# MDCC_1024k.net
KiCad netlist of a schematic drawn in EAGLE
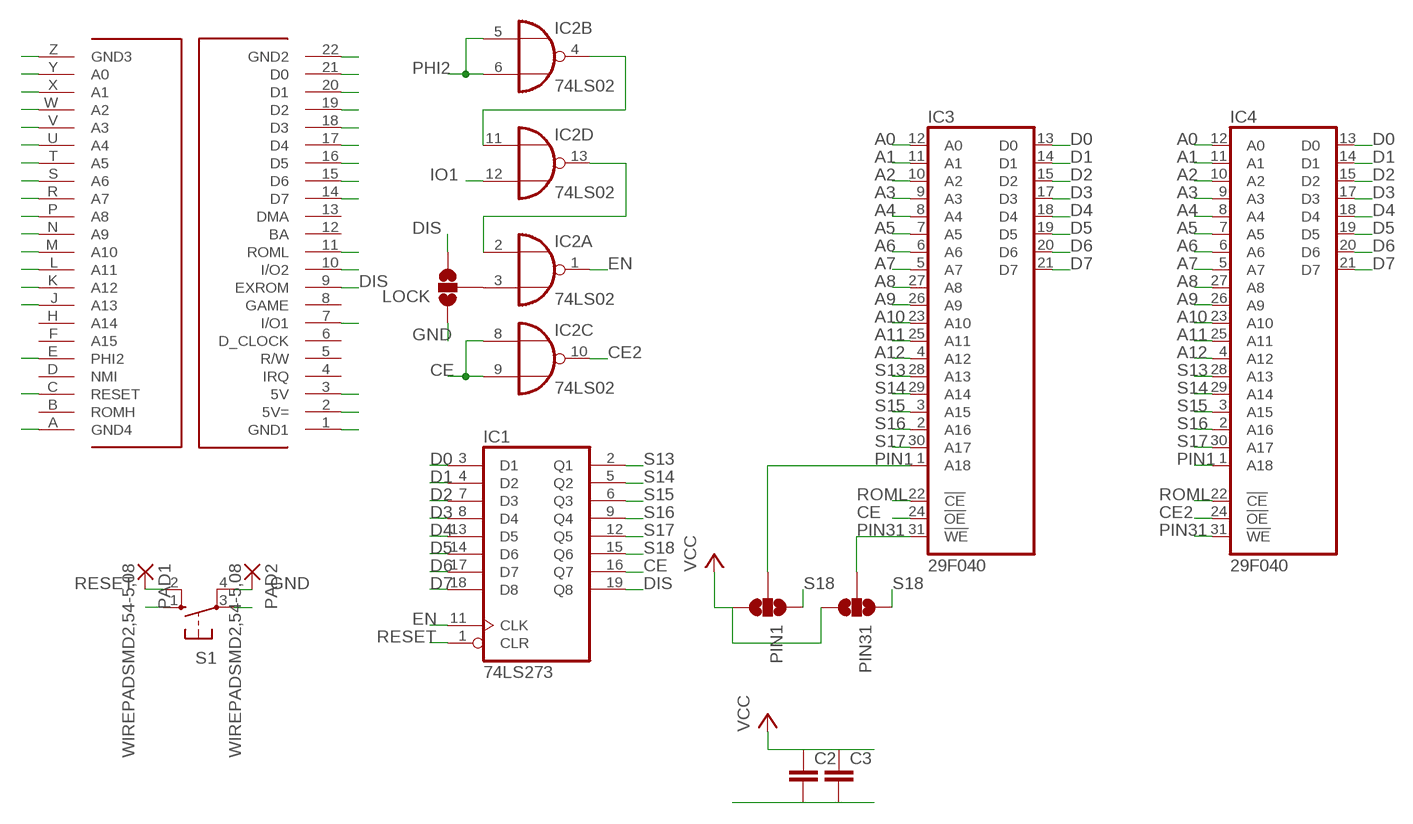
[diagram p0: schematic, sheet 1]

(export (version "E")
  (design (tool "Eeschema 10.0.6"))
  (components
    (comp (ref "C2")
      (value "C-EU025-024X044")
      (footprint "eagle-import:C025-024X044")
      (libsource (lib "eagle-import") (part "C-EU025-024X044"))
    )
    (comp (ref "C3")
      (value "C-EU025-024X044")
      (footprint "eagle-import:C025-024X044")
      (libsource (lib "eagle-import") (part "C-EU025-024X044"))
    )
    (comp (ref "IC1")
      (value "74LS273")
      (footprint "eagle-import:DIL20")
      (libsource (lib "eagle-import") (part "74273NHCT"))
    )
    (comp (ref "IC2")
      (value "74LS02")
      (footprint "eagle-import:DIL14")
      (libsource (lib "eagle-import") (part "7402NLS"))
    )
    (comp (ref "IC3")
      (value "29F040")
      (footprint "eagle-import:DIL32-6")
      (libsource (lib "eagle-import") (part "AM29F040N"))
    )
    (comp (ref "IC4")
      (value "29F040")
      (footprint "eagle-import:DIL32-6")
      (libsource (lib "eagle-import") (part "AM29F040N"))
    )
    (comp (ref "LOCK")
      (value "SOLDERJUMPER_2WAYS")
      (footprint "eagle-import:SJ_3")
      (libsource (lib "eagle-import") (part "SOLDERJUMPER_2WAYS"))
    )
    (comp (ref "PAD1")
      (value "WIREPADSMD2,54-5,08")
      (footprint "eagle-import:SMD2,54-5,08")
      (libsource (lib "eagle-import") (part "WIREPADSMD2,54-5,08"))
    )
    (comp (ref "PAD2")
      (value "WIREPADSMD2,54-5,08")
      (footprint "eagle-import:SMD2,54-5,08")
      (libsource (lib "eagle-import") (part "WIREPADSMD2,54-5,08"))
    )
    (comp (ref "PIN1")
      (value "SOLDERJUMPER_2WAYS")
      (footprint "eagle-import:SJ_3")
      (libsource (lib "eagle-import") (part "SOLDERJUMPER_2WAYS"))
    )
    (comp (ref "PIN31")
      (value "SOLDERJUMPER_2WAYS")
      (footprint "eagle-import:SJ_3")
      (libsource (lib "eagle-import") (part "SOLDERJUMPER_2WAYS"))
    )
    (comp (ref "S1")
      (value "10-XX")
      (footprint "eagle-import:B3F-10XX")
      (fields (field (name "MPN") "B3F-1000"))
      (libsource (lib "eagle-import") (part "10-XX"))
    )
    (comp (ref "U$1")
      (value "C64_EXPANSION__CARTRIDGE")
      (footprint "eagle-import:C64_EXPANSION__CARTRIDGE")
      (libsource (lib "eagle-import") (part "C64_EXPANSION__CARTRIDGE"))
    )
  )
  (nets
    (net (code "1") (name "/A0") (class "Default")
      (node (ref "IC3") (pin "12") (pinfunction "A0_12") (pintype "input"))
      (node (ref "IC4") (pin "12") (pinfunction "A0_12") (pintype "input"))
      (node (ref "U$1") (pin "Y") (pinfunction "A0_Y") (pintype "bidirectional"))
    )
    (net (code "2") (name "/A1") (class "Default")
      (node (ref "IC3") (pin "11") (pinfunction "A1_11") (pintype "input"))
      (node (ref "IC4") (pin "11") (pinfunction "A1_11") (pintype "input"))
      (node (ref "U$1") (pin "X") (pinfunction "A1_X") (pintype "bidirectional"))
    )
    (net (code "3") (name "/A2") (class "Default")
      (node (ref "IC3") (pin "10") (pinfunction "A2_10") (pintype "input"))
      (node (ref "IC4") (pin "10") (pinfunction "A2_10") (pintype "input"))
      (node (ref "U$1") (pin "W") (pinfunction "A2_W") (pintype "bidirectional"))
    )
    (net (code "4") (name "/A3") (class "Default")
      (node (ref "IC3") (pin "9") (pinfunction "A3_9") (pintype "input"))
      (node (ref "IC4") (pin "9") (pinfunction "A3_9") (pintype "input"))
      (node (ref "U$1") (pin "V") (pinfunction "A3_V") (pintype "bidirectional"))
    )
    (net (code "5") (name "/A4") (class "Default")
      (node (ref "IC3") (pin "8") (pinfunction "A4_8") (pintype "input"))
      (node (ref "IC4") (pin "8") (pinfunction "A4_8") (pintype "input"))
      (node (ref "U$1") (pin "U") (pinfunction "A4_U") (pintype "bidirectional"))
    )
    (net (code "6") (name "/A5") (class "Default")
      (node (ref "IC3") (pin "7") (pinfunction "A5_7") (pintype "input"))
      (node (ref "IC4") (pin "7") (pinfunction "A5_7") (pintype "input"))
      (node (ref "U$1") (pin "T") (pinfunction "A5_T") (pintype "bidirectional"))
    )
    (net (code "7") (name "/A6") (class "Default")
      (node (ref "IC3") (pin "6") (pinfunction "A6_6") (pintype "input"))
      (node (ref "IC4") (pin "6") (pinfunction "A6_6") (pintype "input"))
      (node (ref "U$1") (pin "S") (pinfunction "A6_S") (pintype "bidirectional"))
    )
    (net (code "8") (name "/A7") (class "Default")
      (node (ref "IC3") (pin "5") (pinfunction "A7_5") (pintype "input"))
      (node (ref "IC4") (pin "5") (pinfunction "A7_5") (pintype "input"))
      (node (ref "U$1") (pin "R") (pinfunction "A7_R") (pintype "bidirectional"))
    )
    (net (code "9") (name "/A8") (class "Default")
      (node (ref "IC3") (pin "27") (pinfunction "A8_27") (pintype "input"))
      (node (ref "IC4") (pin "27") (pinfunction "A8_27") (pintype "input"))
      (node (ref "U$1") (pin "P") (pinfunction "A8_P") (pintype "bidirectional"))
    )
    (net (code "10") (name "/A9") (class "Default")
      (node (ref "IC3") (pin "26") (pinfunction "A9_26") (pintype "input"))
      (node (ref "IC4") (pin "26") (pinfunction "A9_26") (pintype "input"))
      (node (ref "U$1") (pin "N") (pinfunction "A9_N") (pintype "bidirectional"))
    )
    (net (code "11") (name "/A10") (class "Default")
      (node (ref "IC3") (pin "23") (pinfunction "A10_23") (pintype "input"))
      (node (ref "IC4") (pin "23") (pinfunction "A10_23") (pintype "input"))
      (node (ref "U$1") (pin "M") (pinfunction "A10_M") (pintype "bidirectional"))
    )
    (net (code "12") (name "/A11") (class "Default")
      (node (ref "IC3") (pin "25") (pinfunction "A11_25") (pintype "input"))
      (node (ref "IC4") (pin "25") (pinfunction "A11_25") (pintype "input"))
      (node (ref "U$1") (pin "L") (pinfunction "A11_L") (pintype "bidirectional"))
    )
    (net (code "13") (name "/A12") (class "Default")
      (node (ref "IC3") (pin "4") (pinfunction "A12_4") (pintype "input"))
      (node (ref "IC4") (pin "4") (pinfunction "A12_4") (pintype "input"))
      (node (ref "U$1") (pin "K") (pinfunction "A12_K") (pintype "bidirectional"))
    )
    (net (code "14") (name "/CE") (class "Default")
      (node (ref "IC1") (pin "16") (pinfunction "Q7_16") (pintype "output"))
      (node (ref "IC2") (pin "8") (pinfunction "I0_8") (pintype "input"))
      (node (ref "IC2") (pin "9") (pinfunction "I1_9") (pintype "input"))
      (node (ref "IC3") (pin "24") (pinfunction "~{OE}_24") (pintype "input"))
    )
    (net (code "15") (name "/CE2") (class "Default")
      (node (ref "IC2") (pin "10") (pinfunction "O_10") (pintype "output"))
      (node (ref "IC4") (pin "24") (pinfunction "~{OE}_24") (pintype "input"))
    )
    (net (code "16") (name "/D0") (class "Default")
      (node (ref "IC1") (pin "3") (pinfunction "D1_3") (pintype "input"))
      (node (ref "IC3") (pin "13") (pinfunction "D0_13") (pintype "tri_state"))
      (node (ref "IC4") (pin "13") (pinfunction "D0_13") (pintype "tri_state"))
      (node (ref "U$1") (pin "21") (pinfunction "D0_21") (pintype "bidirectional"))
    )
    (net (code "17") (name "/D1") (class "Default")
      (node (ref "IC1") (pin "4") (pinfunction "D2_4") (pintype "input"))
      (node (ref "IC3") (pin "14") (pinfunction "D1_14") (pintype "tri_state"))
      (node (ref "IC4") (pin "14") (pinfunction "D1_14") (pintype "tri_state"))
      (node (ref "U$1") (pin "20") (pinfunction "D1_20") (pintype "bidirectional"))
    )
    (net (code "18") (name "/D2") (class "Default")
      (node (ref "IC1") (pin "7") (pinfunction "D3_7") (pintype "input"))
      (node (ref "IC3") (pin "15") (pinfunction "D2_15") (pintype "tri_state"))
      (node (ref "IC4") (pin "15") (pinfunction "D2_15") (pintype "tri_state"))
      (node (ref "U$1") (pin "19") (pinfunction "D2_19") (pintype "bidirectional"))
    )
    (net (code "19") (name "/D3") (class "Default")
      (node (ref "IC1") (pin "8") (pinfunction "D4_8") (pintype "input"))
      (node (ref "IC3") (pin "17") (pinfunction "D3_17") (pintype "tri_state"))
      (node (ref "IC4") (pin "17") (pinfunction "D3_17") (pintype "tri_state"))
      (node (ref "U$1") (pin "18") (pinfunction "D3_18") (pintype "bidirectional"))
    )
    (net (code "20") (name "/D4") (class "Default")
      (node (ref "IC1") (pin "13") (pinfunction "D5_13") (pintype "input"))
      (node (ref "IC3") (pin "18") (pinfunction "D4_18") (pintype "tri_state"))
      (node (ref "IC4") (pin "18") (pinfunction "D4_18") (pintype "tri_state"))
      (node (ref "U$1") (pin "17") (pinfunction "D4_17") (pintype "bidirectional"))
    )
    (net (code "21") (name "/D5") (class "Default")
      (node (ref "IC1") (pin "14") (pinfunction "D6_14") (pintype "input"))
      (node (ref "IC3") (pin "19") (pinfunction "D5_19") (pintype "tri_state"))
      (node (ref "IC4") (pin "19") (pinfunction "D5_19") (pintype "tri_state"))
      (node (ref "U$1") (pin "16") (pinfunction "D5_16") (pintype "bidirectional"))
    )
    (net (code "22") (name "/D6") (class "Default")
      (node (ref "IC1") (pin "17") (pinfunction "D7_17") (pintype "input"))
      (node (ref "IC3") (pin "20") (pinfunction "D6_20") (pintype "tri_state"))
      (node (ref "IC4") (pin "20") (pinfunction "D6_20") (pintype "tri_state"))
      (node (ref "U$1") (pin "15") (pinfunction "D6_15") (pintype "bidirectional"))
    )
    (net (code "23") (name "/D7") (class "Default")
      (node (ref "IC1") (pin "18") (pinfunction "D8_18") (pintype "input"))
      (node (ref "IC3") (pin "21") (pinfunction "D7_21") (pintype "tri_state"))
      (node (ref "IC4") (pin "21") (pinfunction "D7_21") (pintype "tri_state"))
      (node (ref "U$1") (pin "14") (pinfunction "D7_14") (pintype "bidirectional"))
    )
    (net (code "24") (name "/DIS") (class "Default")
      (node (ref "IC1") (pin "19") (pinfunction "Q8_19") (pintype "output"))
      (node (ref "LOCK") (pin "3") (pinfunction "3_3") (pintype "passive"))
      (node (ref "U$1") (pin "9") (pinfunction "EXROM_9") (pintype "bidirectional"))
    )
    (net (code "25") (name "/EN") (class "Default")
      (node (ref "IC1") (pin "11") (pinfunction "CLK_11") (pintype "input"))
      (node (ref "IC2") (pin "1") (pinfunction "O_1") (pintype "output"))
    )
    (net (code "26") (name "/GND") (class "Default")
      (node (ref "C2") (pin "2") (pinfunction "2_2") (pintype "passive"))
      (node (ref "C3") (pin "2") (pinfunction "2_2") (pintype "passive"))
      (node (ref "LOCK") (pin "1") (pinfunction "1_1") (pintype "passive"))
      (node (ref "PAD2") (pin "1") (pinfunction "P_1") (pintype "passive"))
      (node (ref "S1") (pin "3") (pinfunction "P_3") (pintype "passive"))
      (node (ref "S1") (pin "4") (pinfunction "P1_4") (pintype "passive"))
      (node (ref "U$1") (pin "1") (pinfunction "GND1_1") (pintype "bidirectional"))
      (node (ref "U$1") (pin "22") (pinfunction "GND2_22") (pintype "bidirectional"))
      (node (ref "U$1") (pin "A") (pinfunction "GND4_A") (pintype "bidirectional"))
      (node (ref "U$1") (pin "Z") (pinfunction "GND3_Z") (pintype "bidirectional"))
    )
    (net (code "27") (name "/IO1") (class "Default")
      (node (ref "IC2") (pin "12") (pinfunction "I1_12") (pintype "input"))
      (node (ref "U$1") (pin "7") (pinfunction "I/O1_7") (pintype "bidirectional"))
    )
    (net (code "28") (name "/PHI2") (class "Default")
      (node (ref "IC2") (pin "5") (pinfunction "I0_5") (pintype "input"))
      (node (ref "IC2") (pin "6") (pinfunction "I1_6") (pintype "input"))
      (node (ref "U$1") (pin "E") (pinfunction "PHI2_E") (pintype "bidirectional"))
    )
    (net (code "29") (name "/PIN1") (class "Default")
      (node (ref "IC3") (pin "1") (pinfunction "A18_1") (pintype "input"))
      (node (ref "IC4") (pin "1") (pinfunction "A18_1") (pintype "input"))
      (node (ref "PIN1") (pin "2") (pinfunction "2_2") (pintype "passive"))
    )
    (net (code "30") (name "/PIN31") (class "Default")
      (node (ref "IC3") (pin "31") (pinfunction "~{WE}_31") (pintype "input"))
      (node (ref "IC4") (pin "31") (pinfunction "~{WE}_31") (pintype "input"))
      (node (ref "PIN31") (pin "2") (pinfunction "2_2") (pintype "passive"))
    )
    (net (code "31") (name "/RESET") (class "Default")
      (node (ref "IC1") (pin "1") (pinfunction "CLR_1") (pintype "input"))
      (node (ref "PAD1") (pin "1") (pinfunction "P_1") (pintype "passive"))
      (node (ref "S1") (pin "1") (pinfunction "S_1") (pintype "passive"))
      (node (ref "S1") (pin "2") (pinfunction "S1_2") (pintype "passive"))
      (node (ref "U$1") (pin "C") (pinfunction "RESET_C") (pintype "bidirectional"))
    )
    (net (code "32") (name "/ROML") (class "Default")
      (node (ref "IC3") (pin "22") (pinfunction "~{CE}_22") (pintype "input"))
      (node (ref "IC4") (pin "22") (pinfunction "~{CE}_22") (pintype "input"))
      (node (ref "U$1") (pin "11") (pinfunction "ROML_11") (pintype "bidirectional"))
    )
    (net (code "33") (name "/S13") (class "Default")
      (node (ref "IC1") (pin "2") (pinfunction "Q1_2") (pintype "output"))
      (node (ref "IC3") (pin "28") (pinfunction "A13_28") (pintype "input"))
      (node (ref "IC4") (pin "28") (pinfunction "A13_28") (pintype "input"))
    )
    (net (code "34") (name "/S14") (class "Default")
      (node (ref "IC1") (pin "5") (pinfunction "Q2_5") (pintype "output"))
      (node (ref "IC3") (pin "29") (pinfunction "A14_29") (pintype "input"))
      (node (ref "IC4") (pin "29") (pinfunction "A14_29") (pintype "input"))
    )
    (net (code "35") (name "/S15") (class "Default")
      (node (ref "IC1") (pin "6") (pinfunction "Q3_6") (pintype "output"))
      (node (ref "IC3") (pin "3") (pinfunction "A15_3") (pintype "input"))
      (node (ref "IC4") (pin "3") (pinfunction "A15_3") (pintype "input"))
    )
    (net (code "36") (name "/S16") (class "Default")
      (node (ref "IC1") (pin "9") (pinfunction "Q4_9") (pintype "output"))
      (node (ref "IC3") (pin "2") (pinfunction "A16_2") (pintype "input"))
      (node (ref "IC4") (pin "2") (pinfunction "A16_2") (pintype "input"))
    )
    (net (code "37") (name "/S17") (class "Default")
      (node (ref "IC1") (pin "12") (pinfunction "Q5_12") (pintype "output"))
      (node (ref "IC3") (pin "30") (pinfunction "A17_30") (pintype "input"))
      (node (ref "IC4") (pin "30") (pinfunction "A17_30") (pintype "input"))
    )
    (net (code "38") (name "/S18") (class "Default")
      (node (ref "IC1") (pin "15") (pinfunction "Q6_15") (pintype "output"))
      (node (ref "PIN1") (pin "1") (pinfunction "1_1") (pintype "passive"))
      (node (ref "PIN31") (pin "1") (pinfunction "1_1") (pintype "passive"))
    )
    (net (code "39") (name "Net-(IC2A-I0)") (class "Default")
      (node (ref "IC2") (pin "13") (pinfunction "O_13") (pintype "output"))
      (node (ref "IC2") (pin "2") (pinfunction "I0_2") (pintype "input"))
    )
    (net (code "40") (name "Net-(IC2A-I1)") (class "Default")
      (node (ref "IC2") (pin "3") (pinfunction "I1_3") (pintype "input"))
      (node (ref "LOCK") (pin "2") (pinfunction "2_2") (pintype "passive"))
    )
    (net (code "41") (name "Net-(IC2B-O)") (class "Default")
      (node (ref "IC2") (pin "11") (pinfunction "I0_11") (pintype "input"))
      (node (ref "IC2") (pin "4") (pinfunction "O_4") (pintype "output"))
    )
    (net (code "42") (name "VCC") (class "Default")
      (node (ref "C2") (pin "1") (pinfunction "1_1") (pintype "passive"))
      (node (ref "C3") (pin "1") (pinfunction "1_1") (pintype "passive"))
      (node (ref "PIN1") (pin "3") (pinfunction "3_3") (pintype "passive"))
      (node (ref "PIN31") (pin "3") (pinfunction "3_3") (pintype "passive"))
      (node (ref "U$1") (pin "2") (pinfunction "5V=_2") (pintype "bidirectional"))
      (node (ref "U$1") (pin "3") (pinfunction "5V_3") (pintype "bidirectional"))
    )
    (net (code "43") (name "unconnected-(U$1-A13-PadJ)") (class "Default")
      (node (ref "U$1") (pin "J") (pinfunction "A13_J") (pintype "bidirectional"))
    )
    (net (code "44") (name "unconnected-(U$1-A14-PadH)") (class "Default")
      (node (ref "U$1") (pin "H") (pinfunction "A14_H") (pintype "bidirectional"))
    )
    (net (code "45") (name "unconnected-(U$1-A15-PadF)") (class "Default")
      (node (ref "U$1") (pin "F") (pinfunction "A15_F") (pintype "bidirectional"))
    )
    (net (code "46") (name "unconnected-(U$1-BA-Pad12)") (class "Default")
      (node (ref "U$1") (pin "12") (pinfunction "BA_12") (pintype "bidirectional"))
    )
    (net (code "47") (name "unconnected-(U$1-DMA-Pad13)") (class "Default")
      (node (ref "U$1") (pin "13") (pinfunction "DMA_13") (pintype "bidirectional"))
    )
    (net (code "48") (name "unconnected-(U$1-D_CLOCK-Pad6)") (class "Default")
      (node (ref "U$1") (pin "6") (pinfunction "D_CLOCK_6") (pintype "bidirectional"))
    )
    (net (code "49") (name "unconnected-(U$1-GAME-Pad8)") (class "Default")
      (node (ref "U$1") (pin "8") (pinfunction "GAME_8") (pintype "bidirectional"))
    )
    (net (code "50") (name "unconnected-(U$1-IRQ-Pad4)") (class "Default")
      (node (ref "U$1") (pin "4") (pinfunction "IRQ_4") (pintype "bidirectional"))
    )
    (net (code "51") (name "unconnected-(U$1-I{slash}O2-Pad10)") (class "Default")
      (node (ref "U$1") (pin "10") (pinfunction "I/O2_10") (pintype "bidirectional"))
    )
    (net (code "52") (name "unconnected-(U$1-NMI-PadD)") (class "Default")
      (node (ref "U$1") (pin "D") (pinfunction "NMI_D") (pintype "bidirectional"))
    )
    (net (code "53") (name "unconnected-(U$1-ROMH-PadB)") (class "Default")
      (node (ref "U$1") (pin "B") (pinfunction "ROMH_B") (pintype "bidirectional"))
    )
    (net (code "54") (name "unconnected-(U$1-R{slash}W-Pad5)") (class "Default")
      (node (ref "U$1") (pin "5") (pinfunction "R/W_5") (pintype "bidirectional"))
    )
  )
)
